# Sheet1.net
KiCad netlist of a schematic drawn in Altium Designer
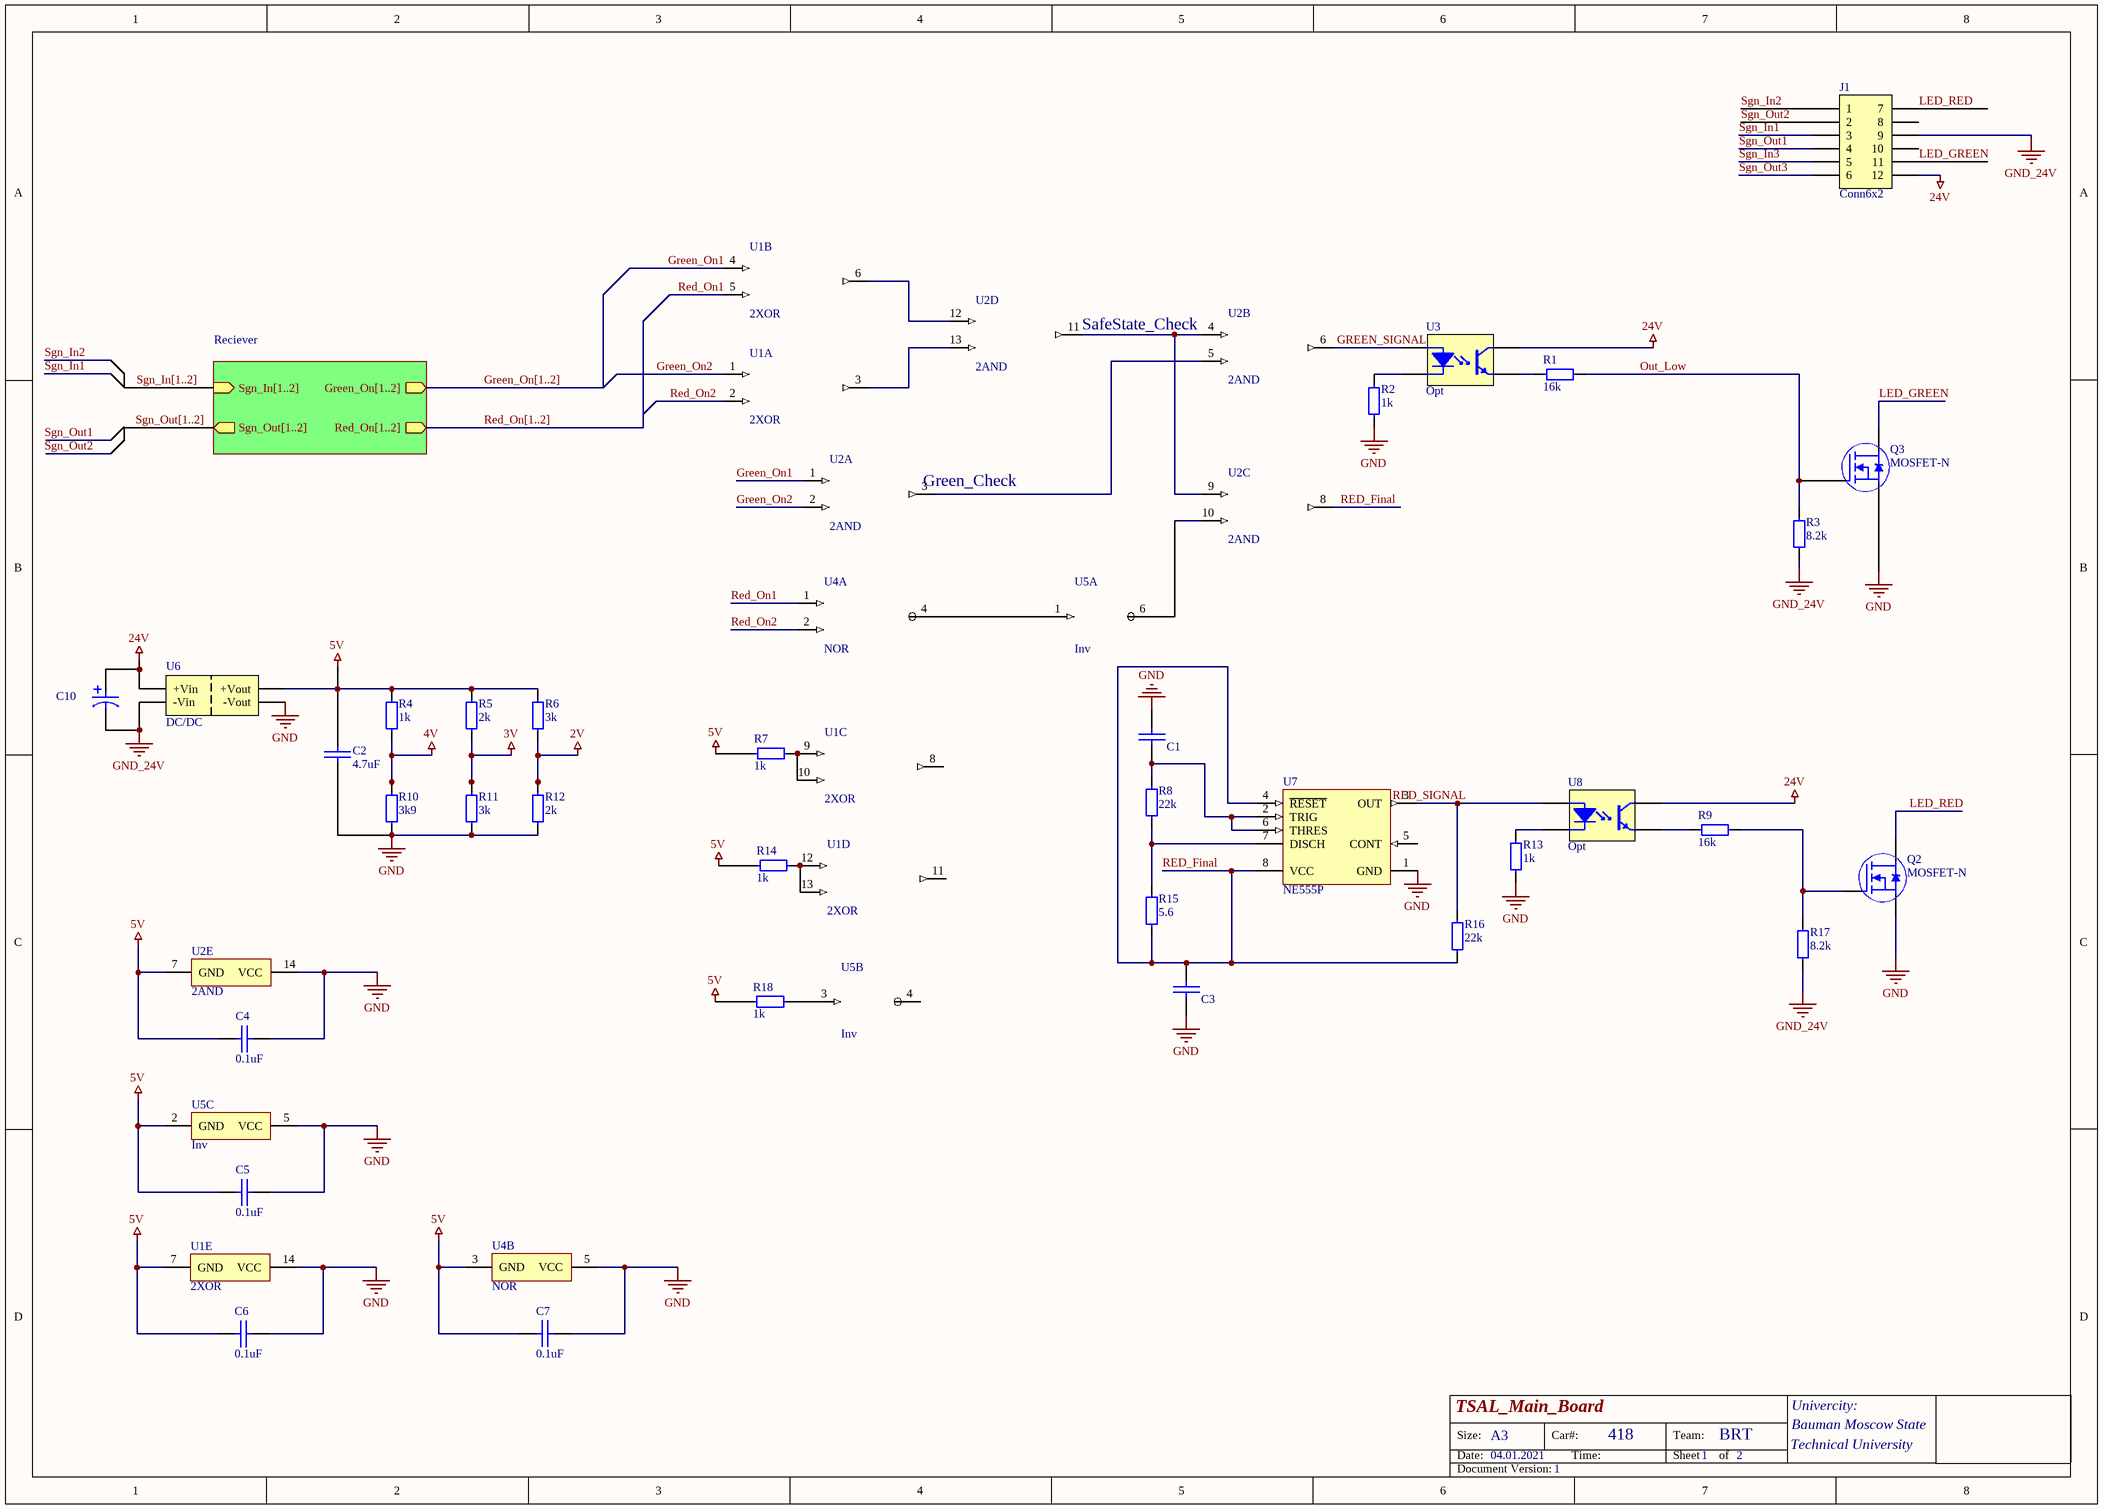
[diagram p0: Sheet1.SchDoc]

(export (version "E")
  (design (tool "Eeschema 10.0.6"))
  (components
    (comp (ref "C1")
      (value "Cap 10nF (0805)")
      (footprint "0805 Capicator")
      (description "0805 X7R 10nF 100V 10%")
      (fields
        (field (name "PART NUMBER") "GRM21BR72A103KA01L")
        (field (name "MANUFACTURER") "Murata Manufacturing")
        (field (name "SOURCE") "Karen_Components.SchLib")
      )
      (libsource (lib "Bauman Racing Team") (part "Symbol"))
    )
    (comp (ref "C2")
      (value "4.7uF")
      (footprint "0603 Capicator")
      (description "4.7uF X5R 6.3V 10% 0603")
      (fields
        (field (name "MANUFACTURER") "Murata Manufacturing")
        (field (name "PART NUMBER") "GRM188R60J475KE19D")
      )
      (libsource (lib "BRT_Components") (part "Cap 4.7uF (0603)"))
    )
    (comp (ref "C3")
      (value "Cap 10nF (0805)")
      (footprint "0805 Capicator")
      (description "0805 X7R 10nF 100V 10%")
      (fields
        (field (name "PART NUMBER") "GRM21BR72A103KA01L")
        (field (name "MANUFACTURER") "Murata Manufacturing")
        (field (name "SOURCE") "Karen_Components.SchLib")
      )
      (libsource (lib "Bauman Racing Team") (part "Symbol"))
    )
    (comp (ref "C4")
      (value "0.1uF")
      (footprint "0805 Capicator")
      (description "0.1uF X7R 50V 10% 0805")
      (fields
        (field (name "MANUFACTURER") "Murata Manufacturing")
        (field (name "PART NUMBER") "GRM21BR71E104KA01L")
      )
      (libsource (lib "BRT_Components") (part "Cap 0.1uF (0805)"))
    )
    (comp (ref "C5")
      (value "0.1uF")
      (footprint "0805 Capicator")
      (description "0.1uF X7R 50V 10% 0805")
      (fields
        (field (name "MANUFACTURER") "Murata Manufacturing")
        (field (name "PART NUMBER") "GRM21BR71E104KA01L")
      )
      (libsource (lib "BRT_Components") (part "Cap 0.1uF (0805)"))
    )
    (comp (ref "C6")
      (value "0.1uF")
      (footprint "0805 Capicator")
      (description "0.1uF X7R 50V 10% 0805")
      (fields
        (field (name "MANUFACTURER") "Murata Manufacturing")
        (field (name "PART NUMBER") "GRM21BR71E104KA01L")
      )
      (libsource (lib "BRT_Components") (part "Cap 0.1uF (0805)"))
    )
    (comp (ref "C7")
      (value "0.1uF")
      (footprint "0805 Capicator")
      (description "0.1uF X7R 50V 10% 0805")
      (fields
        (field (name "MANUFACTURER") "Murata Manufacturing")
        (field (name "PART NUMBER") "GRM21BR71E104KA01L")
      )
      (libsource (lib "BRT_Components") (part "Cap 0.1uF (0805)"))
    )
    (comp (ref "C10")
      (value "Cap Pol 4.7uF")
      (footprint "Bar Cap 4x5.4")
      (description "ECAP SMD,  35V, 105°C")
      (fields
        (field (name "MANUFACTURER") "Epcos")
        (field (name "PART NUMBER") "B41121A7475M000")
        (field (name "SOURCE") "Karen_Components.SchLib")
      )
      (libsource (lib "") (part "Symbol_1"))
    )
    (comp (ref "J1")
      (value "Conn6x2")
      (footprint "Conn6x2(Molex)")
      (libsource (lib "BRT_Components") (part "Conn 12 [Stack64]"))
    )
    (comp (ref "Q2")
      (value "MOSFET-N")
      (footprint "D-Pak (TO-252AA)")
      (description "Trans MOSFET N-CH Si 55V 89A 3-Pin(2+Tab) DPAK Tube")
      (fields
        (field (name "PART NUMBER") "IRLR3705ZTRPBF")
        (field (name "MANUFACTURER") "International Rectifier")
      )
      (libsource (lib "BRT_Components") (part "MOSFET-N [IRLR]"))
    )
    (comp (ref "Q3")
      (value "MOSFET-N")
      (footprint "D-Pak (TO-252AA)")
      (description "Trans MOSFET N-CH Si 55V 89A 3-Pin(2+Tab) DPAK Tube")
      (fields
        (field (name "PART NUMBER") "IRLR3705ZTRPBF")
        (field (name "MANUFACTURER") "International Rectifier")
      )
      (libsource (lib "BRT_Components") (part "MOSFET-N [IRLR]"))
    )
    (comp (ref "R1")
      (value "16k")
      (footprint "0603 Resistor")
      (description "0.1W 0603 16k, 1%")
      (fields (field (name "MANUFACTURER") "Taiwan") (field (name "PART NUMBER") "RC0603FR-0716KL"))
      (libsource (lib "Schlib1") (part "Res 16k (0603)"))
    )
    (comp (ref "R2")
      (value "1k")
      (footprint "0603 Resistor")
      (description "0.1W 0603 1k, 1%")
      (fields (field (name "PART NUMBER") "RC0603FR-071KL") (field (name "MANUFACTURER") "Taiwan"))
      (libsource (lib "BRT_Components") (part "Res 1k (0603)"))
    )
    (comp (ref "R3")
      (value "8.2k")
      (footprint "0603 Resistor")
      (description "0.1W 0603 8.2k, 1%")
      (fields (field (name "MANUFACTURER") "Taiwan") (field (name "PART NUMBER") "RC0603FR-078R2L"))
      (libsource (lib "Schlib1") (part "Res 8.2k (0603)"))
    )
    (comp (ref "R4")
      (value "1k")
      (footprint "0603 Resistor")
      (description "0.1W 0603 1k, 1%")
      (fields (field (name "PART NUMBER") "RC0603FR-071KL") (field (name "MANUFACTURER") "Taiwan"))
      (libsource (lib "BRT_Components") (part "Res 1k (0603)"))
    )
    (comp (ref "R5")
      (value "2k")
      (footprint "0603 Resistor")
      (description "0.1W 0603 2k, 1%")
      (fields (field (name "PART NUMBER") "RC0603FR-072KL") (field (name "MANUFACTURER") "Taiwan"))
      (libsource (lib "BRT_Components") (part "Res 2k (0603)"))
    )
    (comp (ref "R6")
      (value "3k")
      (footprint "0603 Resistor")
      (description "0.1W 0603 3k, 1%")
      (fields (field (name "PART NUMBER") "RC0603FR-073KL") (field (name "MANUFACTURER") "Taiwan"))
      (libsource (lib "BRT_Components") (part "Res 3k (0603)"))
    )
    (comp (ref "R7")
      (value "1k")
      (footprint "0603 Resistor")
      (description "0.1W 0603 1k, 1%")
      (fields (field (name "PART NUMBER") "RC0603FR-071KL") (field (name "MANUFACTURER") "Taiwan"))
      (libsource (lib "BRT_Components") (part "Res 1k (0603)"))
    )
    (comp (ref "R8")
      (value "22k")
      (footprint "0603 Resistor")
      (description "0.1W 0603 22k, 1%")
      (libsource (lib "Main") (part "Res 22k (0.1W 0603 22k, 1%)"))
    )
    (comp (ref "R9")
      (value "16k")
      (footprint "0603 Resistor")
      (description "0.1W 0603 16k, 1%")
      (fields (field (name "MANUFACTURER") "Taiwan") (field (name "PART NUMBER") "RC0603FR-0716KL"))
      (libsource (lib "Schlib1") (part "Res 16k (0603)"))
    )
    (comp (ref "R10")
      (value "3k9")
      (footprint "0603 Resistor")
      (description "0.1W 0603 3.9k, 1%")
      (fields (field (name "PART NUMBER") "RC0603FR-073K9L") (field (name "MANUFACTURER") "Taiwan"))
      (libsource (lib "BRT_Components") (part "Res 3.9k (0603)"))
    )
    (comp (ref "R11")
      (value "3k")
      (footprint "0603 Resistor")
      (description "0.1W 0603 3k, 1%")
      (fields (field (name "PART NUMBER") "RC0603FR-073KL") (field (name "MANUFACTURER") "Taiwan"))
      (libsource (lib "BRT_Components") (part "Res 3k (0603)"))
    )
    (comp (ref "R12")
      (value "2k")
      (footprint "0603 Resistor")
      (description "0.1W 0603 2k, 1%")
      (fields (field (name "PART NUMBER") "RC0603FR-072KL") (field (name "MANUFACTURER") "Taiwan"))
      (libsource (lib "BRT_Components") (part "Res 2k (0603)"))
    )
    (comp (ref "R13")
      (value "1k")
      (footprint "0603 Resistor")
      (description "0.1W 0603 1k, 1%")
      (fields (field (name "PART NUMBER") "RC0603FR-071KL") (field (name "MANUFACTURER") "Taiwan"))
      (libsource (lib "BRT_Components") (part "Res 1k (0603)"))
    )
    (comp (ref "R14")
      (value "1k")
      (footprint "0603 Resistor")
      (description "0.1W 0603 1k, 1%")
      (fields (field (name "PART NUMBER") "RC0603FR-071KL") (field (name "MANUFACTURER") "Taiwan"))
      (libsource (lib "BRT_Components") (part "Res 1k (0603)"))
    )
    (comp (ref "R15")
      (value "5.6")
      (footprint "0603 Resistor")
      (description "0.1W 0603 5.6k, 1%")
      (libsource (lib "Main") (part "Res 5.6k (0.1W 0603 5.6k, 1%)"))
    )
    (comp (ref "R16")
      (value "22k")
      (footprint "0603 Resistor")
      (description "0.1W 0603 22k, 1%")
      (libsource (lib "Main") (part "Res 22k (0.1W 0603 22k, 1%)"))
    )
    (comp (ref "R17")
      (value "8.2k")
      (footprint "0603 Resistor")
      (description "0.1W 0603 8.2k, 1%")
      (fields (field (name "MANUFACTURER") "Taiwan") (field (name "PART NUMBER") "RC0603FR-078R2L"))
      (libsource (lib "Schlib1") (part "Res 8.2k (0603)"))
    )
    (comp (ref "R18")
      (value "1k")
      (footprint "0603 Resistor")
      (description "0.1W 0603 1k, 1%")
      (fields (field (name "PART NUMBER") "RC0603FR-071KL") (field (name "MANUFACTURER") "Taiwan"))
      (libsource (lib "BRT_Components") (part "Res 1k (0603)"))
    )
    (comp (ref "U1") (value "2XOR") (footprint "SOIC-14") (libsource (lib "TSAL") (part "4 (2XOR)")))
    (comp (ref "U2") (value "2AND") (footprint "SOIC-14") (libsource (lib "TSAL") (part "4 (2AND)")))
    (comp (ref "U3")
      (value "Opt")
      (footprint "FAIR-MDIP-4_V")
      (fields (field (name "MANUFACTURER") "ON Semiconductor"))
      (libsource (lib "BRT_Components") (part "Optocoupler [FOD817B]"))
    )
    (comp (ref "U4") (value "NOR") (footprint "SOT-23-5") (libsource (lib "TSAL") (part "NOR")))
    (comp (ref "U5") (value "Inv") (footprint "SOT236") (libsource (lib "TSAL") (part "Inverter")))
    (comp (ref "U6")
      (value "DC/DC")
      (footprint "SIP7")
      (fields (field (name "MANUFACTURER") "Traco Power") (field (name "PART NUMBER") "TMH2405S"))
      (libsource (lib "BRT_Components") (part "DC/DC Isolated 5V [TMH]"))
    )
    (comp (ref "U7")
      (value "NE555P")
      (footprint "SOIC-8")
      (description "Standard Timer Single 8-Pin PDIP Tube")
      (fields (field (name "MANUFACTURER") "Texas Instruments"))
      (libsource (lib "TSAL") (part "NE555P"))
    )
    (comp (ref "U8")
      (value "Opt")
      (footprint "FAIR-MDIP-4_V")
      (fields (field (name "MANUFACTURER") "ON Semiconductor"))
      (libsource (lib "BRT_Components") (part "Optocoupler [FOD817B]"))
    )
  )
  (nets
    (net (code "1") (name "/GREEN_SIGNAL") (class "Default")
      (node (ref "U2") (pin "6") (pinfunction "Y_6") (pintype "output"))
      (node (ref "U3") (pin "1") (pinfunction "ANODE_1") (pintype "passive"))
    )
    (net (code "2") (name "/Green_On1") (class "Default")
      (node (ref "U1") (pin "4") (pinfunction "A_4") (pintype "input"))
      (node (ref "U2") (pin "1") (pinfunction "A_1") (pintype "input"))
    )
    (net (code "3") (name "/Green_On2") (class "Default")
      (node (ref "U1") (pin "1") (pinfunction "A_1") (pintype "input"))
      (node (ref "U2") (pin "2") (pinfunction "B_2") (pintype "input"))
    )
    (net (code "5") (name "/LED_GREEN") (class "Default")
      (node (ref "J1") (pin "11") (pinfunction "11_11") (pintype "passive"))
      (node (ref "Q3") (pin "2") (pinfunction "Drain_2") (pintype "passive"))
    )
    (net (code "6") (name "/LED_RED") (class "Default")
      (node (ref "J1") (pin "7") (pinfunction "7_7") (pintype "passive"))
      (node (ref "Q2") (pin "2") (pinfunction "Drain_2") (pintype "passive"))
    )
    (net (code "7") (name "/Out_Low") (class "Default")
      (node (ref "Q3") (pin "1") (pinfunction "Gate_1") (pintype "passive"))
      (node (ref "R1") (pin "2") (pinfunction "2_2") (pintype "passive"))
      (node (ref "R3") (pin "2") (pinfunction "2_2") (pintype "passive"))
    )
    (net (code "8") (name "/RED_Final") (class "Default")
      (node (ref "C3") (pin "2") (pinfunction "2_2") (pintype "passive"))
      (node (ref "R15") (pin "1") (pinfunction "1_1") (pintype "passive"))
      (node (ref "R16") (pin "1") (pinfunction "1_1") (pintype "passive"))
      (node (ref "U2") (pin "8") (pinfunction "Y_8") (pintype "output"))
      (node (ref "U7") (pin "4") (pinfunction "~{RESET}_4") (pintype "input"))
      (node (ref "U7") (pin "8") (pinfunction "VCC_8") (pintype "power_in"))
    )
    (net (code "9") (name "/RED_SIGNAL") (class "Default")
      (node (ref "R16") (pin "2") (pinfunction "2_2") (pintype "passive"))
      (node (ref "U7") (pin "3") (pinfunction "OUT_3") (pintype "output"))
      (node (ref "U8") (pin "1") (pinfunction "ANODE_1") (pintype "passive"))
    )
    (net (code "10") (name "/Red_On1") (class "Default")
      (node (ref "U1") (pin "5") (pinfunction "B_5") (pintype "input"))
      (node (ref "U4") (pin "1") (pinfunction "A_1") (pintype "input"))
    )
    (net (code "11") (name "/Red_On2") (class "Default")
      (node (ref "U1") (pin "2") (pinfunction "B_2") (pintype "input"))
      (node (ref "U4") (pin "2") (pinfunction "B_2") (pintype "input"))
    )
    (net (code "13") (name "/Sgn_In1") (class "Default")
      (node (ref "J1") (pin "3") (pinfunction "3_3") (pintype "passive"))
    )
    (net (code "14") (name "/Sgn_In2") (class "Default")
      (node (ref "J1") (pin "1") (pinfunction "1_1") (pintype "passive"))
    )
    (net (code "15") (name "/Sgn_In3") (class "Default")
      (node (ref "J1") (pin "5") (pinfunction "5_5") (pintype "passive"))
    )
    (net (code "17") (name "/Sgn_Out1") (class "Default")
      (node (ref "J1") (pin "4") (pinfunction "4_4") (pintype "passive"))
    )
    (net (code "18") (name "/Sgn_Out2") (class "Default")
      (node (ref "J1") (pin "2") (pinfunction "2_2") (pintype "passive"))
    )
    (net (code "19") (name "/Sgn_Out3") (class "Default")
      (node (ref "J1") (pin "6") (pinfunction "6_6") (pintype "passive"))
    )
    (net (code "21") (name "2V") (class "Default")
      (node (ref "R12") (pin "2") (pinfunction "2_2") (pintype "passive"))
      (node (ref "R6") (pin "1") (pinfunction "1_1") (pintype "passive"))
    )
    (net (code "22") (name "3V") (class "Default")
      (node (ref "R11") (pin "2") (pinfunction "2_2") (pintype "passive"))
      (node (ref "R5") (pin "1") (pinfunction "1_1") (pintype "passive"))
    )
    (net (code "23") (name "4V") (class "Default")
      (node (ref "R10") (pin "2") (pinfunction "2_2") (pintype "passive"))
      (node (ref "R4") (pin "2") (pinfunction "2_2") (pintype "passive"))
    )
    (net (code "24") (name "5V") (class "Default")
      (node (ref "C2") (pin "2") (pinfunction "2_2") (pintype "passive"))
      (node (ref "C4") (pin "1") (pinfunction "1_1") (pintype "passive"))
      (node (ref "C5") (pin "1") (pinfunction "1_1") (pintype "passive"))
      (node (ref "C6") (pin "1") (pinfunction "1_1") (pintype "passive"))
      (node (ref "C7") (pin "1") (pinfunction "1_1") (pintype "passive"))
      (node (ref "R14") (pin "2") (pinfunction "2_2") (pintype "passive"))
      (node (ref "R18") (pin "2") (pinfunction "2_2") (pintype "passive"))
      (node (ref "R4") (pin "1") (pinfunction "1_1") (pintype "passive"))
      (node (ref "R5") (pin "2") (pinfunction "2_2") (pintype "passive"))
      (node (ref "R6") (pin "2") (pinfunction "2_2") (pintype "passive"))
      (node (ref "R7") (pin "2") (pinfunction "2_2") (pintype "passive"))
      (node (ref "U1") (pin "7") (pinfunction "GND_7") (pintype "passive"))
      (node (ref "U2") (pin "7") (pinfunction "GND_7") (pintype "passive"))
      (node (ref "U4") (pin "3") (pinfunction "GND_3") (pintype "passive"))
      (node (ref "U5") (pin "2") (pinfunction "GND_2") (pintype "passive"))
      (node (ref "U6") (pin "6") (pinfunction "+Vout_6") (pintype "power_in"))
    )
    (net (code "25") (name "24V") (class "Default")
      (node (ref "C10") (pin "2") (pinfunction "2_2") (pintype "passive"))
      (node (ref "J1") (pin "12") (pinfunction "12_12") (pintype "passive"))
      (node (ref "U3") (pin "4") (pinfunction "COLLECTOR_4") (pintype "passive"))
      (node (ref "U6") (pin "1") (pinfunction "+Vin_1") (pintype "power_in"))
      (node (ref "U8") (pin "4") (pinfunction "COLLECTOR_4") (pintype "passive"))
    )
    (net (code "26") (name "GND") (class "Default")
      (node (ref "C1") (pin "2") (pinfunction "2_2") (pintype "passive"))
      (node (ref "C2") (pin "1") (pinfunction "1_1") (pintype "passive"))
      (node (ref "C3") (pin "1") (pinfunction "1_1") (pintype "passive"))
      (node (ref "C4") (pin "2") (pinfunction "2_2") (pintype "passive"))
      (node (ref "C5") (pin "2") (pinfunction "2_2") (pintype "passive"))
      (node (ref "C6") (pin "2") (pinfunction "2_2") (pintype "passive"))
      (node (ref "C7") (pin "2") (pinfunction "2_2") (pintype "passive"))
      (node (ref "Q2") (pin "3") (pinfunction "Source_3") (pintype "passive"))
      (node (ref "Q3") (pin "3") (pinfunction "Source_3") (pintype "passive"))
      (node (ref "R10") (pin "1") (pinfunction "1_1") (pintype "passive"))
      (node (ref "R11") (pin "1") (pinfunction "1_1") (pintype "passive"))
      (node (ref "R12") (pin "1") (pinfunction "1_1") (pintype "passive"))
      (node (ref "R13") (pin "1") (pinfunction "1_1") (pintype "passive"))
      (node (ref "R2") (pin "1") (pinfunction "1_1") (pintype "passive"))
      (node (ref "U1") (pin "14") (pinfunction "VCC_14") (pintype "passive"))
      (node (ref "U2") (pin "14") (pinfunction "VCC_14") (pintype "passive"))
      (node (ref "U4") (pin "5") (pinfunction "VCC_5") (pintype "passive"))
      (node (ref "U5") (pin "5") (pinfunction "VCC_5") (pintype "passive"))
      (node (ref "U6") (pin "4") (pinfunction "-Vout_4") (pintype "power_in"))
      (node (ref "U7") (pin "1") (pinfunction "GND_1") (pintype "power_in"))
    )
    (net (code "27") (name "GND_24V") (class "Default")
      (node (ref "C10") (pin "1") (pinfunction "1_1") (pintype "passive"))
      (node (ref "J1") (pin "9") (pinfunction "9_9") (pintype "passive"))
      (node (ref "R17") (pin "1") (pinfunction "1_1") (pintype "passive"))
      (node (ref "R3") (pin "1") (pinfunction "1_1") (pintype "passive"))
      (node (ref "U6") (pin "2") (pinfunction "-Vin_2") (pintype "power_in"))
    )
    (net (code "28") (name "Net-(Q2-Gate)") (class "Default")
      (node (ref "Q2") (pin "1") (pinfunction "Gate_1") (pintype "passive"))
      (node (ref "R17") (pin "2") (pinfunction "2_2") (pintype "passive"))
      (node (ref "R9") (pin "2") (pinfunction "2_2") (pintype "passive"))
    )
    (net (code "29") (name "Net-(U1A-Y)") (class "Default")
      (node (ref "U1") (pin "3") (pinfunction "Y_3") (pintype "output"))
      (node (ref "U2") (pin "13") (pinfunction "B_13") (pintype "input"))
    )
    (net (code "30") (name "Net-(U1B-Y)") (class "Default")
      (node (ref "U1") (pin "6") (pinfunction "Y_6") (pintype "output"))
      (node (ref "U2") (pin "12") (pinfunction "A_12") (pintype "input"))
    )
    (net (code "31") (name "Net-(U1C-A)") (class "Default")
      (node (ref "R7") (pin "1") (pinfunction "1_1") (pintype "passive"))
      (node (ref "U1") (pin "10") (pinfunction "B_10") (pintype "input"))
      (node (ref "U1") (pin "9") (pinfunction "A_9") (pintype "input"))
    )
    (net (code "32") (name "Net-(U1D-A)") (class "Default")
      (node (ref "R14") (pin "1") (pinfunction "1_1") (pintype "passive"))
      (node (ref "U1") (pin "12") (pinfunction "A_12") (pintype "input"))
      (node (ref "U1") (pin "13") (pinfunction "B_13") (pintype "input"))
    )
    (net (code "33") (name "Net-(U2A-Y)") (class "Default")
      (node (ref "U2") (pin "3") (pinfunction "Y_3") (pintype "output"))
      (node (ref "U2") (pin "5") (pinfunction "B_5") (pintype "input"))
    )
    (net (code "34") (name "Net-(U2B-A)") (class "Default")
      (node (ref "U2") (pin "11") (pinfunction "Y_11") (pintype "output"))
      (node (ref "U2") (pin "4") (pinfunction "A_4") (pintype "input"))
      (node (ref "U2") (pin "9") (pinfunction "A_9") (pintype "input"))
    )
    (net (code "35") (name "Net-(U2C-B)") (class "Default")
      (node (ref "U2") (pin "10") (pinfunction "B_10") (pintype "input"))
      (node (ref "U5") (pin "6") (pinfunction "Y_6") (pintype "passive"))
    )
    (net (code "36") (name "Net-(U3-CATHODE)") (class "Default")
      (node (ref "R2") (pin "2") (pinfunction "2_2") (pintype "passive"))
      (node (ref "U3") (pin "2") (pinfunction "CATHODE_2") (pintype "passive"))
    )
    (net (code "37") (name "Net-(U3-EMITTER)") (class "Default")
      (node (ref "R1") (pin "1") (pinfunction "1_1") (pintype "passive"))
      (node (ref "U3") (pin "3") (pinfunction "EMITTER_3") (pintype "passive"))
    )
    (net (code "38") (name "Net-(U4A-Y)") (class "Default")
      (node (ref "U4") (pin "4") (pinfunction "Y_4") (pintype "passive"))
      (node (ref "U5") (pin "1") (pinfunction "A_1") (pintype "input"))
    )
    (net (code "39") (name "Net-(U5B-A)") (class "Default")
      (node (ref "R18") (pin "1") (pinfunction "1_1") (pintype "passive"))
      (node (ref "U5") (pin "3") (pinfunction "A_3") (pintype "input"))
    )
    (net (code "40") (name "Net-(U7-DISCH)") (class "Default")
      (node (ref "R15") (pin "2") (pinfunction "2_2") (pintype "passive"))
      (node (ref "R8") (pin "1") (pinfunction "1_1") (pintype "passive"))
      (node (ref "U7") (pin "7") (pinfunction "DISCH_7") (pintype "open_collector"))
    )
    (net (code "41") (name "Net-(U7-THRES)") (class "Default")
      (node (ref "C1") (pin "1") (pinfunction "1_1") (pintype "passive"))
      (node (ref "R8") (pin "2") (pinfunction "2_2") (pintype "passive"))
      (node (ref "U7") (pin "2") (pinfunction "TRIG_2") (pintype "input"))
      (node (ref "U7") (pin "6") (pinfunction "THRES_6") (pintype "input"))
    )
    (net (code "42") (name "Net-(U8-CATHODE)") (class "Default")
      (node (ref "R13") (pin "2") (pinfunction "2_2") (pintype "passive"))
      (node (ref "U8") (pin "2") (pinfunction "CATHODE_2") (pintype "passive"))
    )
    (net (code "43") (name "Net-(U8-EMITTER)") (class "Default")
      (node (ref "R9") (pin "1") (pinfunction "1_1") (pintype "passive"))
      (node (ref "U8") (pin "3") (pinfunction "EMITTER_3") (pintype "passive"))
    )
    (net (code "44") (name "unconnected-(J1-Pad8)") (class "Default")
      (node (ref "J1") (pin "8") (pinfunction "8_8") (pintype "passive"))
    )
    (net (code "45") (name "unconnected-(J1-Pad10)") (class "Default")
      (node (ref "J1") (pin "10") (pinfunction "10_10") (pintype "passive"))
    )
    (net (code "46") (name "unconnected-(U1C-Y-Pad8)") (class "Default")
      (node (ref "U1") (pin "8") (pinfunction "Y_8") (pintype "output"))
    )
    (net (code "47") (name "unconnected-(U1D-Y-Pad11)") (class "Default")
      (node (ref "U1") (pin "11") (pinfunction "Y_11") (pintype "output"))
    )
    (net (code "48") (name "unconnected-(U5B-Y-Pad4)") (class "Default")
      (node (ref "U5") (pin "4") (pinfunction "Y_4") (pintype "passive"))
    )
    (net (code "49") (name "unconnected-(U7-CONT-Pad5)") (class "Default")
      (node (ref "U7") (pin "5") (pinfunction "CONT_5") (pintype "input"))
    )
  )
)
